# SCH_N3_FLIGHT_COMPUTER_2023-10-18_1.net
KiCad netlist of a schematic drawn in EasyEDA
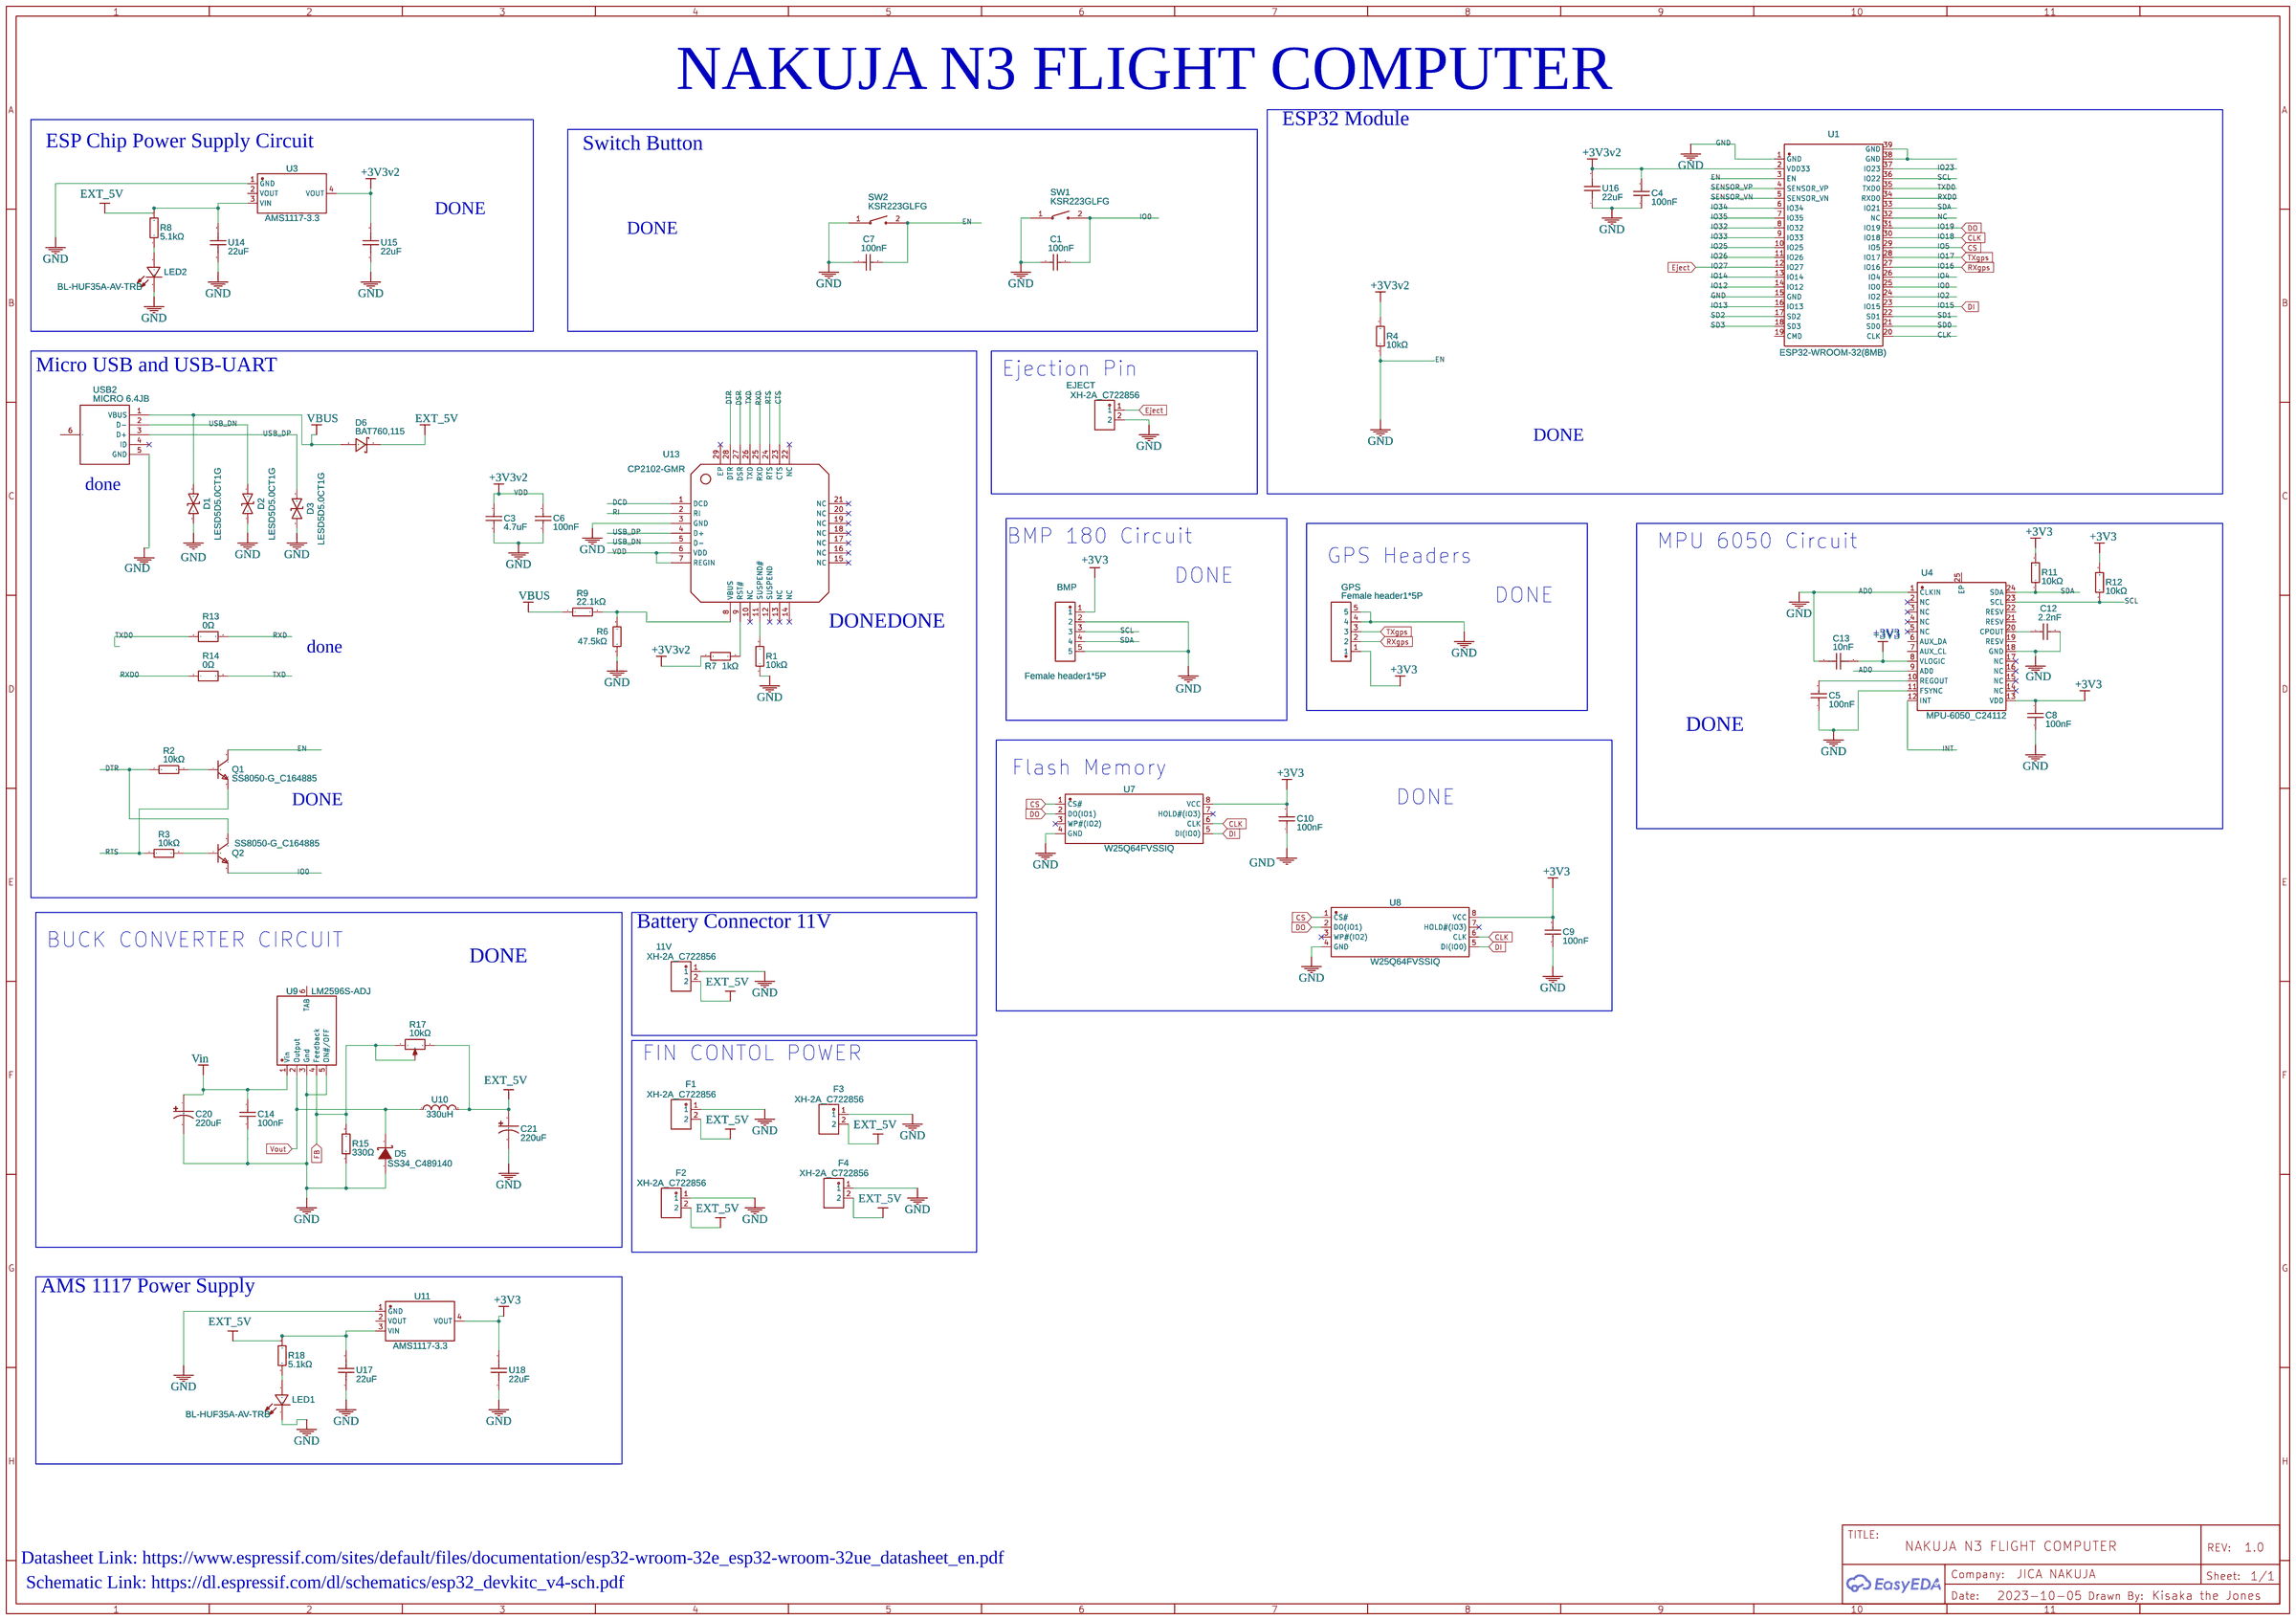
[diagram p0: schematic sheet]

(export (version "E")
  (design (tool "Eeschema 10.0.6"))
  (components
    (comp (ref "11V")
      (value "XH-2A_C722856")
      (fields (field (name "Manufacturer Part") "XH-2A") (field (name "Manufacturer") "CAX"))
      (libsource (lib "") (part "XH-2A_C722856_2"))
    )
    (comp (ref "BMP")
      (value "Female header1*5P")
      (fields (field (name "Manufacturer Part") "2.0-1*5P母") (field (name "Manufacturer") "BOOMELE(博穆精密)"))
      (libsource (lib "") (part "Female header1*5P"))
    )
    (comp (ref "C1")
      (value "100nF")
      (fields (field (name "Manufacturer Part") "FN15X104K160PNG") (field (name "Manufacturer") "PSA(信昌电陶)"))
      (libsource (lib "") (part "FN15X104K160PNG_1"))
    )
    (comp (ref "C3")
      (value "4.7uF")
      (fields
        (field (name "Manufacturer Part") "CL21B475KPFNNNE")
        (field (name "Manufacturer") "SAMSUNG(三星)")
      )
      (libsource (lib "") (part "CL21B475KPFNNNE"))
    )
    (comp (ref "C4")
      (value "100nF")
      (fields (field (name "Manufacturer Part") "FN15X104K160PNG") (field (name "Manufacturer") "PSA(信昌电陶)"))
      (libsource (lib "") (part "FN15X104K160PNG"))
    )
    (comp (ref "C5")
      (value "100nF")
      (fields (field (name "Manufacturer Part") "FN15X104K160PNG") (field (name "Manufacturer") "PSA(信昌电陶)"))
      (libsource (lib "") (part "FN15X104K160PNG"))
    )
    (comp (ref "C6")
      (value "100nF")
      (fields (field (name "Manufacturer Part") "FN15X104K160PNG") (field (name "Manufacturer") "PSA(信昌电陶)"))
      (libsource (lib "") (part "FN15X104K160PNG"))
    )
    (comp (ref "C7")
      (value "100nF")
      (fields (field (name "Manufacturer Part") "FN15X104K160PNG") (field (name "Manufacturer") "PSA(信昌电陶)"))
      (libsource (lib "") (part "FN15X104K160PNG_1"))
    )
    (comp (ref "C8")
      (value "100nF")
      (fields (field (name "Manufacturer Part") "FN15X104K160PNG") (field (name "Manufacturer") "PSA(信昌电陶)"))
      (libsource (lib "") (part "FN15X104K160PNG"))
    )
    (comp (ref "C9")
      (value "100nF")
      (fields (field (name "Manufacturer Part") "FN15X104K160PNG") (field (name "Manufacturer") "PSA(信昌电陶)"))
      (libsource (lib "") (part "FN15X104K160PNG"))
    )
    (comp (ref "C10")
      (value "100nF")
      (fields (field (name "Manufacturer Part") "FN15X104K160PNG") (field (name "Manufacturer") "PSA(信昌电陶)"))
      (libsource (lib "") (part "FN15X104K160PNG"))
    )
    (comp (ref "C12")
      (value "2.2nF")
      (fields (field (name "Manufacturer Part") "0805B222K500NT") (field (name "Manufacturer") "FH(风华)"))
      (libsource (lib "") (part "0805B222K500NT"))
    )
    (comp (ref "C13")
      (value "10nF")
      (fields
        (field (name "Manufacturer Part") "CC0805KRX7R9BB103")
        (field (name "Manufacturer") "YAGEO(国巨)")
      )
      (libsource (lib "") (part "CC0805KRX7R9BB103"))
    )
    (comp (ref "C14")
      (value "100nF")
      (fields (field (name "Manufacturer Part") "FN15X104K160PNG") (field (name "Manufacturer") "PSA(信昌电陶)"))
      (libsource (lib "") (part "FN15X104K160PNG"))
    )
    (comp (ref "C20")
      (value "220uF")
      (fields (field (name "Manufacturer Part") "EEEFP1H221AP") (field (name "Manufacturer") "PANASONIC(松下)"))
      (libsource (lib "") (part "EEEFP1H221AP"))
    )
    (comp (ref "C21")
      (value "220uF")
      (fields (field (name "Manufacturer Part") "EEEFP1H221AP") (field (name "Manufacturer") "PANASONIC(松下)"))
      (libsource (lib "") (part "EEEFP1H221AP"))
    )
    (comp (ref "D1")
      (value "LESD5D5.0CT1G")
      (fields (field (name "Manufacturer") "LRC(乐山无线电)"))
      (libsource (lib "") (part "LESD5D5.0CT1G"))
    )
    (comp (ref "D2")
      (value "LESD5D5.0CT1G")
      (fields (field (name "Manufacturer") "LRC(乐山无线电)"))
      (libsource (lib "") (part "LESD5D5.0CT1G"))
    )
    (comp (ref "D3")
      (value "LESD5D5.0CT1G")
      (fields (field (name "Manufacturer") "LRC(乐山无线电)"))
      (libsource (lib "") (part "LESD5D5.0CT1G"))
    )
    (comp (ref "D5")
      (value "SS34_C489140")
      (fields (field (name "Manufacturer Part") "SS34") (field (name "Manufacturer") "KEXIN(科信)"))
      (libsource (lib "") (part "SS34_C489140"))
    )
    (comp (ref "D6")
      (value "BAT760,115")
      (fields (field (name "Manufacturer") "Nexperia(安世)"))
      (libsource (lib "") (part "BAT760,115"))
    )
    (comp (ref "EJECT")
      (value "XH-2A_C722856")
      (fields (field (name "Manufacturer Part") "XH-2A") (field (name "Manufacturer") "CAX"))
      (libsource (lib "") (part "XH-2A_C722856_1"))
    )
    (comp (ref "F1")
      (value "XH-2A_C722856")
      (fields (field (name "Manufacturer Part") "XH-2A") (field (name "Manufacturer") "CAX"))
      (libsource (lib "") (part "XH-2A_C722856"))
    )
    (comp (ref "F2")
      (value "XH-2A_C722856")
      (fields (field (name "Manufacturer Part") "XH-2A") (field (name "Manufacturer") "CAX"))
      (libsource (lib "") (part "XH-2A_C722856"))
    )
    (comp (ref "F3")
      (value "XH-2A_C722856")
      (fields (field (name "Manufacturer Part") "XH-2A") (field (name "Manufacturer") "CAX"))
      (libsource (lib "") (part "XH-2A_C722856"))
    )
    (comp (ref "F4")
      (value "XH-2A_C722856")
      (fields (field (name "Manufacturer Part") "XH-2A") (field (name "Manufacturer") "CAX"))
      (libsource (lib "") (part "XH-2A_C722856"))
    )
    (comp (ref "GPS")
      (value "Female header1*5P")
      (fields (field (name "Manufacturer Part") "2.0-1*5P母") (field (name "Manufacturer") "BOOMELE(博穆精密)"))
      (libsource (lib "") (part "Female header1*5P_1"))
    )
    (comp (ref "LED1")
      (value "BL-HUF35A-AV-TRB")
      (fields (field (name "Manufacturer") "BrtLed(佰鸿)"))
      (libsource (lib "") (part "BL-HUF35A-AV-TRB"))
    )
    (comp (ref "LED2")
      (value "BL-HUF35A-AV-TRB")
      (fields (field (name "Manufacturer") "BrtLed(佰鸿)"))
      (libsource (lib "") (part "BL-HUF35A-AV-TRB"))
    )
    (comp (ref "Q1")
      (value "SS8050-G_C164885")
      (fields (field (name "Manufacturer Part") "SS8050-G") (field (name "Manufacturer") "CJ(江苏长电/长晶)"))
      (libsource (lib "") (part "SS8050-G_C164885"))
    )
    (comp (ref "Q2")
      (value "SS8050-G_C164885")
      (fields (field (name "Manufacturer Part") "SS8050-G") (field (name "Manufacturer") "CJ(江苏长电/长晶)"))
      (libsource (lib "") (part "SS8050-G_C164885"))
    )
    (comp (ref "R1")
      (value "10kΩ")
      (fields
        (field (name "Manufacturer Part") "QR1206J10K0P05Z")
        (field (name "Manufacturer") "EVER OHMS(天二科技)")
      )
      (libsource (lib "") (part "QR1206J10KP05_1"))
    )
    (comp (ref "R2")
      (value "10kΩ")
      (fields
        (field (name "Manufacturer Part") "QR1206J10K0P05Z")
        (field (name "Manufacturer") "EVER OHMS(天二科技)")
      )
      (libsource (lib "") (part "QR1206J10KP05"))
    )
    (comp (ref "R3")
      (value "10kΩ")
      (fields
        (field (name "Manufacturer Part") "QR1206J10K0P05Z")
        (field (name "Manufacturer") "EVER OHMS(天二科技)")
      )
      (libsource (lib "") (part "QR1206J10KP05"))
    )
    (comp (ref "R4")
      (value "10kΩ")
      (fields
        (field (name "Manufacturer Part") "QR1206J10K0P05Z")
        (field (name "Manufacturer") "EVER OHMS(天二科技)")
      )
      (libsource (lib "") (part "QR1206J10KP05_1"))
    )
    (comp (ref "R6")
      (value "47.5kΩ")
      (fields
        (field (name "Manufacturer Part") "0402WGF4752TCE")
        (field (name "Manufacturer") "UNI-ROYAL(厚声)")
      )
      (libsource (lib "") (part "0402WGF4752TCE"))
    )
    (comp (ref "R7")
      (value "1kΩ")
      (fields
        (field (name "Manufacturer Part") "0402WGF1001TCE")
        (field (name "Manufacturer") "UNI-ROYAL(厚声)")
      )
      (libsource (lib "") (part "0402WGF1001TCE"))
    )
    (comp (ref "R8")
      (value "5.1kΩ")
      (fields
        (field (name "Manufacturer Part") "0402WGJ0512TCE")
        (field (name "Manufacturer") "UNI-ROYAL(厚声)")
      )
      (libsource (lib "") (part "0402WGJ0512TCE"))
    )
    (comp (ref "R9")
      (value "22.1kΩ")
      (fields
        (field (name "Manufacturer Part") "0402WGF2212TCE")
        (field (name "Manufacturer") "UNI-ROYAL(厚声)")
      )
      (libsource (lib "") (part "0402WGF2212TCE"))
    )
    (comp (ref "R11")
      (value "10kΩ")
      (fields
        (field (name "Manufacturer Part") "QR1206J10K0P05Z")
        (field (name "Manufacturer") "EVER OHMS(天二科技)")
      )
      (libsource (lib "") (part "QR1206J10KP05_1"))
    )
    (comp (ref "R12")
      (value "10kΩ")
      (fields
        (field (name "Manufacturer Part") "QR1206J10K0P05Z")
        (field (name "Manufacturer") "EVER OHMS(天二科技)")
      )
      (libsource (lib "") (part "QR1206J10KP05_1"))
    )
    (comp (ref "R13")
      (value "0Ω")
      (fields
        (field (name "Manufacturer Part") "CR0402F0R00Q10Z")
        (field (name "Manufacturer") "EVER OHMS(天二科技)")
      )
      (libsource (lib "") (part "CR0402F0R00Q10Z"))
    )
    (comp (ref "R14")
      (value "0Ω")
      (fields
        (field (name "Manufacturer Part") "CR0402F0R00Q10Z")
        (field (name "Manufacturer") "EVER OHMS(天二科技)")
      )
      (libsource (lib "") (part "CR0402F0R00Q10Z"))
    )
    (comp (ref "R15")
      (value "330Ω")
      (fields (field (name "Manufacturer Part") "RK73B1JTTD331J") (field (name "Manufacturer") "KOA"))
      (libsource (lib "") (part "RK73B1JTTD331J"))
    )
    (comp (ref "R17")
      (value "10kΩ")
      (fields (field (name "Manufacturer Part") "3296W-1-103LF") (field (name "Manufacturer") "BOURNS"))
      (libsource (lib "") (part "3296W-1-103LF"))
    )
    (comp (ref "R18")
      (value "5.1kΩ")
      (fields
        (field (name "Manufacturer Part") "0402WGJ0512TCE")
        (field (name "Manufacturer") "UNI-ROYAL(厚声)")
      )
      (libsource (lib "") (part "0402WGJ0512TCE"))
    )
    (comp (ref "SW1")
      (value "KSR223GLFG")
      (fields (field (name "Manufacturer") "C&K"))
      (libsource (lib "") (part "KSR223GLFG"))
    )
    (comp (ref "SW2")
      (value "KSR223GLFG")
      (fields (field (name "Manufacturer") "C&K"))
      (libsource (lib "") (part "KSR223GLFG"))
    )
    (comp (ref "U1")
      (value "ESP32-WROOM-32(8MB)")
      (fields
        (field (name "Manufacturer Part") "ESP32-WROOM-32-N8")
        (field (name "Manufacturer") "ESPRESSIF(乐鑫)")
      )
      (libsource (lib "") (part "ESP32-WROOM-32(8MB)"))
    )
    (comp (ref "U3")
      (value "AMS1117-3.3")
      (fields (field (name "Manufacturer") "AMS"))
      (libsource (lib "") (part "AMS1117-3.3"))
    )
    (comp (ref "U4")
      (value "MPU-6050_C24112")
      (fields
        (field (name "Manufacturer Part") "MPU-6050")
        (field (name "Manufacturer") "TDK InvenSense(应美盛)")
      )
      (libsource (lib "") (part "MPU-6050_C24112"))
    )
    (comp (ref "U7")
      (value "W25Q64FVSSIQ")
      (fields (field (name "Manufacturer") "WINBOND(华邦)"))
      (libsource (lib "") (part "W25Q64FVSSIQ"))
    )
    (comp (ref "U8")
      (value "W25Q64FVSSIQ")
      (fields (field (name "Manufacturer") "WINBOND(华邦)"))
      (libsource (lib "") (part "W25Q64FVSSIQ"))
    )
    (comp (ref "U9")
      (value "LM2596S-ADJ")
      (fields (field (name "Manufacturer") "UMW(友台半导体)"))
      (libsource (lib "") (part "LM2596S-ADJ"))
    )
    (comp (ref "U10")
      (value "330uH")
      (fields (field (name "Manufacturer Part") "SLF12575T-331M1R0-H") (field (name "Manufacturer") "TDK"))
      (libsource (lib "") (part "SLF12575T-331M1R0-H"))
    )
    (comp (ref "U11")
      (value "AMS1117-3.3")
      (fields (field (name "Manufacturer") "AMS"))
      (libsource (lib "") (part "AMS1117-3.3"))
    )
    (comp (ref "U13")
      (value "CP2102-GMR")
      (fields (field (name "Manufacturer") "SILICON LABS(芯科)"))
      (libsource (lib "") (part "CP2102-GMR"))
    )
    (comp (ref "U14")
      (value "22uF")
      (fields
        (field (name "Manufacturer Part") "V226M0805X5R100NHP")
        (field (name "Manufacturer") "VIIYONG(微容)")
      )
      (libsource (lib "") (part "V226M0805X5R100NHP"))
    )
    (comp (ref "U15")
      (value "22uF")
      (fields
        (field (name "Manufacturer Part") "V226M0805X5R100NHP")
        (field (name "Manufacturer") "VIIYONG(微容)")
      )
      (libsource (lib "") (part "V226M0805X5R100NHP"))
    )
    (comp (ref "U16")
      (value "22uF")
      (fields
        (field (name "Manufacturer Part") "V226M0805X5R100NHP")
        (field (name "Manufacturer") "VIIYONG(微容)")
      )
      (libsource (lib "") (part "V226M0805X5R100NHP"))
    )
    (comp (ref "U17")
      (value "22uF")
      (fields
        (field (name "Manufacturer Part") "V226M0805X5R100NHP")
        (field (name "Manufacturer") "VIIYONG(微容)")
      )
      (libsource (lib "") (part "V226M0805X5R100NHP"))
    )
    (comp (ref "U18")
      (value "22uF")
      (fields
        (field (name "Manufacturer Part") "V226M0805X5R100NHP")
        (field (name "Manufacturer") "VIIYONG(微容)")
      )
      (libsource (lib "") (part "V226M0805X5R100NHP"))
    )
    (comp (ref "USB2")
      (value "MICRO 6.4JB")
      (fields (field (name "Manufacturer") "SHOU HAN(首韩)"))
      (libsource (lib "") (part "MICRO 6.4JB"))
    )
  )
  (nets
    (net (code "1") (name "+3V3") (class "Default")
      (node (ref "BMP") (pin "1") (pinfunction "1_1") (pintype "unspecified"))
      (node (ref "C10") (pin "2") (pinfunction "2_2") (pintype "input"))
      (node (ref "C13") (pin "2") (pinfunction "2_2") (pintype "unspecified"))
      (node (ref "C8") (pin "2") (pinfunction "2_2") (pintype "input"))
      (node (ref "C9") (pin "2") (pinfunction "2_2") (pintype "input"))
      (node (ref "GPS") (pin "1") (pinfunction "1_1") (pintype "unspecified"))
      (node (ref "R11") (pin "2") (pinfunction "2_2") (pintype "unspecified"))
      (node (ref "R12") (pin "2") (pinfunction "2_2") (pintype "unspecified"))
      (node (ref "U11") (pin "4") (pinfunction "VOUT_4") (pintype "unspecified"))
      (node (ref "U18") (pin "2") (pinfunction "2_2") (pintype "unspecified"))
      (node (ref "U4") (pin "13") (pinfunction "VDD_13") (pintype "unspecified"))
      (node (ref "U4") (pin "8") (pinfunction "VLOGIC_8") (pintype "unspecified"))
      (node (ref "U7") (pin "8") (pinfunction "VCC_8") (pintype "unspecified"))
      (node (ref "U8") (pin "8") (pinfunction "VCC_8") (pintype "unspecified"))
    )
    (net (code "2") (name "+3V3v2") (class "Default")
      (node (ref "C3") (pin "2") (pinfunction "2_2") (pintype "input"))
      (node (ref "C4") (pin "2") (pinfunction "2_2") (pintype "input"))
      (node (ref "C6") (pin "2") (pinfunction "2_2") (pintype "input"))
      (node (ref "R4") (pin "2") (pinfunction "2_2") (pintype "unspecified"))
      (node (ref "R7") (pin "1") (pinfunction "1_1") (pintype "input"))
      (node (ref "U1") (pin "2") (pinfunction "VDD33_2") (pintype "unspecified"))
      (node (ref "U13") (pin "6") (pinfunction "VDD_6") (pintype "unspecified"))
      (node (ref "U13") (pin "7") (pinfunction "REGIN_7") (pintype "unspecified"))
      (node (ref "U15") (pin "2") (pinfunction "2_2") (pintype "unspecified"))
      (node (ref "U16") (pin "2") (pinfunction "2_2") (pintype "unspecified"))
      (node (ref "U3") (pin "4") (pinfunction "VOUT_4") (pintype "unspecified"))
    )
    (net (code "3") (name "/CTS") (class "Default")
      (node (ref "U13") (pin "23") (pinfunction "CTS_23") (pintype "unspecified"))
    )
    (net (code "4") (name "/DCD") (class "Default")
      (node (ref "U13") (pin "1") (pinfunction "DCD_1") (pintype "unspecified"))
    )
    (net (code "5") (name "/DSR") (class "Default")
      (node (ref "U13") (pin "27") (pinfunction "DSR_27") (pintype "unspecified"))
    )
    (net (code "6") (name "/DTR") (class "Default")
      (node (ref "Q2") (pin "3") (pinfunction "C_3") (pintype "unspecified"))
      (node (ref "R2") (pin "1") (pinfunction "1_1") (pintype "unspecified"))
      (node (ref "U13") (pin "28") (pinfunction "DTR_28") (pintype "unspecified"))
    )
    (net (code "7") (name "/INT") (class "Default")
      (node (ref "U4") (pin "12") (pinfunction "INT_12") (pintype "unspecified"))
    )
    (net (code "8") (name "/IO0") (class "Default")
      (node (ref "C1") (pin "2") (pinfunction "2_2") (pintype "input"))
      (node (ref "Q2") (pin "2") (pinfunction "E_2") (pintype "unspecified"))
      (node (ref "SW1") (pin "2") (pinfunction "2_2") (pintype "unspecified"))
      (node (ref "U1") (pin "25") (pinfunction "IO0_25") (pintype "unspecified"))
    )
    (net (code "9") (name "/IO2") (class "Default")
      (node (ref "U1") (pin "24") (pinfunction "IO2_24") (pintype "unspecified"))
    )
    (net (code "10") (name "/IO4") (class "Default")
      (node (ref "U1") (pin "26") (pinfunction "IO4_26") (pintype "unspecified"))
    )
    (net (code "11") (name "/IO12") (class "Default")
      (node (ref "U1") (pin "14") (pinfunction "IO12_14") (pintype "unspecified"))
    )
    (net (code "12") (name "/IO13") (class "Default")
      (node (ref "U1") (pin "16") (pinfunction "IO13_16") (pintype "unspecified"))
    )
    (net (code "13") (name "/IO14") (class "Default")
      (node (ref "U1") (pin "13") (pinfunction "IO14_13") (pintype "unspecified"))
    )
    (net (code "14") (name "/IO23") (class "Default")
      (node (ref "U1") (pin "37") (pinfunction "IO23_37") (pintype "unspecified"))
    )
    (net (code "15") (name "/IO25") (class "Default")
      (node (ref "U1") (pin "10") (pinfunction "IO25_10") (pintype "unspecified"))
    )
    (net (code "16") (name "/IO26") (class "Default")
      (node (ref "U1") (pin "11") (pinfunction "IO26_11") (pintype "unspecified"))
    )
    (net (code "17") (name "/IO32") (class "Default")
      (node (ref "U1") (pin "8") (pinfunction "IO32_8") (pintype "unspecified"))
    )
    (net (code "18") (name "/IO33") (class "Default")
      (node (ref "U1") (pin "9") (pinfunction "IO33_9") (pintype "unspecified"))
    )
    (net (code "19") (name "/IO34") (class "Default")
      (node (ref "U1") (pin "6") (pinfunction "IO34_6") (pintype "unspecified"))
    )
    (net (code "20") (name "/IO35") (class "Default")
      (node (ref "U1") (pin "7") (pinfunction "IO35_7") (pintype "unspecified"))
    )
    (net (code "21") (name "/NC") (class "Default")
      (node (ref "U1") (pin "32") (pinfunction "NC_32") (pintype "unspecified"))
    )
    (net (code "22") (name "/RI") (class "Default")
      (node (ref "U13") (pin "2") (pinfunction "RI_2") (pintype "unspecified"))
    )
    (net (code "23") (name "/RTS") (class "Default")
      (node (ref "Q1") (pin "2") (pinfunction "E_2") (pintype "unspecified"))
      (node (ref "R3") (pin "1") (pinfunction "1_1") (pintype "unspecified"))
      (node (ref "U13") (pin "24") (pinfunction "RTS_24") (pintype "unspecified"))
    )
    (net (code "24") (name "/RXD") (class "Default")
      (node (ref "R13") (pin "2") (pinfunction "2_2") (pintype "unspecified"))
      (node (ref "U13") (pin "25") (pinfunction "RXD_25") (pintype "unspecified"))
    )
    (net (code "25") (name "/RXD0") (class "Default")
      (node (ref "R14") (pin "1") (pinfunction "1_1") (pintype "unspecified"))
      (node (ref "U1") (pin "34") (pinfunction "RXD0_34") (pintype "unspecified"))
    )
    (net (code "26") (name "/SCL") (class "Default")
      (node (ref "BMP") (pin "3") (pinfunction "3_3") (pintype "unspecified"))
      (node (ref "R12") (pin "1") (pinfunction "1_1") (pintype "unspecified"))
      (node (ref "U1") (pin "36") (pinfunction "IO22_36") (pintype "unspecified"))
      (node (ref "U4") (pin "23") (pinfunction "SCL_23") (pintype "unspecified"))
    )
    (net (code "27") (name "/SD0") (class "Default")
      (node (ref "U1") (pin "21") (pinfunction "SD0_21") (pintype "unspecified"))
    )
    (net (code "28") (name "/SD1") (class "Default")
      (node (ref "U1") (pin "22") (pinfunction "SD1_22") (pintype "unspecified"))
    )
    (net (code "29") (name "/SD2") (class "Default")
      (node (ref "U1") (pin "17") (pinfunction "SD2_17") (pintype "unspecified"))
    )
    (net (code "30") (name "/SD3") (class "Default")
      (node (ref "U1") (pin "18") (pinfunction "SD3_18") (pintype "unspecified"))
    )
    (net (code "31") (name "/SDA") (class "Default")
      (node (ref "BMP") (pin "4") (pinfunction "4_4") (pintype "unspecified"))
      (node (ref "R11") (pin "1") (pinfunction "1_1") (pintype "unspecified"))
      (node (ref "U1") (pin "33") (pinfunction "IO21_33") (pintype "unspecified"))
      (node (ref "U4") (pin "24") (pinfunction "SDA_24") (pintype "unspecified"))
    )
    (net (code "32") (name "/SENSOR_VN") (class "Default")
      (node (ref "U1") (pin "5") (pinfunction "SENSOR_VN_5") (pintype "unspecified"))
    )
    (net (code "33") (name "/SENSOR_VP") (class "Default")
      (node (ref "U1") (pin "4") (pinfunction "SENSOR_VP_4") (pintype "unspecified"))
    )
    (net (code "34") (name "/TXD") (class "Default")
      (node (ref "R14") (pin "2") (pinfunction "2_2") (pintype "unspecified"))
      (node (ref "U13") (pin "26") (pinfunction "TXD_26") (pintype "unspecified"))
    )
    (net (code "35") (name "/TXD0") (class "Default")
      (node (ref "R13") (pin "1") (pinfunction "1_1") (pintype "unspecified"))
      (node (ref "U1") (pin "35") (pinfunction "TXD0_35") (pintype "unspecified"))
    )
    (net (code "36") (name "/USB_DN") (class "Default")
      (node (ref "D2") (pin "2") (pinfunction "2_2") (pintype "unspecified"))
      (node (ref "U13") (pin "5") (pinfunction "D-_5") (pintype "unspecified"))
      (node (ref "USB2") (pin "2") (pinfunction "D-_2") (pintype "input"))
    )
    (net (code "37") (name "/USB_DP") (class "Default")
      (node (ref "D3") (pin "2") (pinfunction "2_2") (pintype "unspecified"))
      (node (ref "U13") (pin "4") (pinfunction "D+_4") (pintype "unspecified"))
      (node (ref "USB2") (pin "3") (pinfunction "D+_3") (pintype "input"))
    )
    (net (code "38") (name "CLK") (class "Default")
      (node (ref "U1") (pin "20") (pinfunction "CLK_20") (pintype "unspecified"))
      (node (ref "U1") (pin "30") (pinfunction "IO18_30") (pintype "unspecified"))
      (node (ref "U7") (pin "6") (pinfunction "CLK_6") (pintype "unspecified"))
      (node (ref "U8") (pin "6") (pinfunction "CLK_6") (pintype "unspecified"))
    )
    (net (code "39") (name "CS") (class "Default")
      (node (ref "U1") (pin "29") (pinfunction "IO5_29") (pintype "unspecified"))
      (node (ref "U7") (pin "1") (pinfunction "CS#_1") (pintype "unspecified"))
      (node (ref "U8") (pin "1") (pinfunction "CS#_1") (pintype "unspecified"))
    )
    (net (code "40") (name "DI") (class "Default")
      (node (ref "U1") (pin "23") (pinfunction "IO15_23") (pintype "unspecified"))
      (node (ref "U7") (pin "5") (pinfunction "DI(IO0)_5") (pintype "unspecified"))
      (node (ref "U8") (pin "5") (pinfunction "DI(IO0)_5") (pintype "unspecified"))
    )
    (net (code "41") (name "DO") (class "Default")
      (node (ref "U1") (pin "31") (pinfunction "IO19_31") (pintype "unspecified"))
      (node (ref "U7") (pin "2") (pinfunction "DO(IO1)_2") (pintype "unspecified"))
      (node (ref "U8") (pin "2") (pinfunction "DO(IO1)_2") (pintype "unspecified"))
    )
    (net (code "42") (name "EXT_5V") (class "Default")
      (node (ref "11V") (pin "2") (pinfunction "2_2") (pintype "unspecified"))
      (node (ref "C21") (pin "1") (pinfunction "1_1") (pintype "unspecified"))
      (node (ref "D6") (pin "1") (pinfunction "K_1") (pintype "unspecified"))
      (node (ref "F1") (pin "2") (pinfunction "2_2") (pintype "unspecified"))
      (node (ref "F2") (pin "2") (pinfunction "2_2") (pintype "unspecified"))
      (node (ref "F3") (pin "2") (pinfunction "2_2") (pintype "unspecified"))
      (node (ref "F4") (pin "2") (pinfunction "2_2") (pintype "unspecified"))
      (node (ref "R17") (pin "3") (pinfunction "3_3") (pintype "input"))
      (node (ref "R18") (pin "2") (pinfunction "2_2") (pintype "input"))
      (node (ref "R8") (pin "2") (pinfunction "2_2") (pintype "input"))
      (node (ref "U10") (pin "2") (pinfunction "2_2") (pintype "unspecified"))
      (node (ref "U11") (pin "3") (pinfunction "VIN_3") (pintype "unspecified"))
      (node (ref "U14") (pin "2") (pinfunction "2_2") (pintype "unspecified"))
      (node (ref "U17") (pin "2") (pinfunction "2_2") (pintype "unspecified"))
      (node (ref "U3") (pin "3") (pinfunction "VIN_3") (pintype "unspecified"))
    )
    (net (code "43") (name "Eject") (class "Default")
      (node (ref "EJECT") (pin "1") (pinfunction "1_1") (pintype "unspecified"))
      (node (ref "U1") (pin "12") (pinfunction "IO27_12") (pintype "unspecified"))
    )
    (net (code "44") (name "FB") (class "Default")
      (node (ref "R15") (pin "2") (pinfunction "2_2") (pintype "input"))
      (node (ref "R17") (pin "1") (pinfunction "1_1") (pintype "input"))
      (node (ref "R17") (pin "2") (pinfunction "2_2") (pintype "input"))
      (node (ref "U9") (pin "4") (pinfunction "Feedback_4") (pintype "unspecified"))
    )
    (net (code "45") (name "GND") (class "Default")
      (node (ref "11V") (pin "1") (pinfunction "1_1") (pintype "unspecified"))
      (node (ref "BMP") (pin "2") (pinfunction "2_2") (pintype "unspecified"))
      (node (ref "BMP") (pin "5") (pinfunction "5_5") (pintype "unspecified"))
      (node (ref "C1") (pin "1") (pinfunction "1_1") (pintype "input"))
      (node (ref "C10") (pin "1") (pinfunction "1_1") (pintype "input"))
      (node (ref "C12") (pin "2") (pinfunction "2_2") (pintype "input"))
      (node (ref "C13") (pin "1") (pinfunction "1_1") (pintype "unspecified"))
      (node (ref "C14") (pin "1") (pinfunction "1_1") (pintype "input"))
      (node (ref "C20") (pin "2") (pinfunction "2_2") (pintype "unspecified"))
      (node (ref "C21") (pin "2") (pinfunction "2_2") (pintype "unspecified"))
      (node (ref "C3") (pin "1") (pinfunction "1_1") (pintype "input"))
      (node (ref "C4") (pin "1") (pinfunction "1_1") (pintype "input"))
      (node (ref "C5") (pin "1") (pinfunction "1_1") (pintype "input"))
      (node (ref "C6") (pin "1") (pinfunction "1_1") (pintype "input"))
      (node (ref "C7") (pin "1") (pinfunction "1_1") (pintype "input"))
      (node (ref "C7") (pin "2") (pinfunction "2_2") (pintype "input"))
      (node (ref "C8") (pin "1") (pinfunction "1_1") (pintype "input"))
      (node (ref "C9") (pin "1") (pinfunction "1_1") (pintype "input"))
      (node (ref "D1") (pin "1") (pinfunction "1_1") (pintype "unspecified"))
      (node (ref "D2") (pin "1") (pinfunction "1_1") (pintype "unspecified"))
      (node (ref "D3") (pin "1") (pinfunction "1_1") (pintype "unspecified"))
      (node (ref "D5") (pin "2") (pinfunction "A_2") (pintype "unspecified"))
      (node (ref "EJECT") (pin "2") (pinfunction "2_2") (pintype "unspecified"))
      (node (ref "F1") (pin "1") (pinfunction "1_1") (pintype "unspecified"))
      (node (ref "F2") (pin "1") (pinfunction "1_1") (pintype "unspecified"))
      (node (ref "F3") (pin "1") (pinfunction "1_1") (pintype "unspecified"))
      (node (ref "F4") (pin "1") (pinfunction "1_1") (pintype "unspecified"))
      (node (ref "GPS") (pin "4") (pinfunction "4_4") (pintype "unspecified"))
      (node (ref "GPS") (pin "5") (pinfunction "5_5") (pintype "unspecified"))
      (node (ref "LED1") (pin "1") (pinfunction "C_1") (pintype "unspecified"))
      (node (ref "LED2") (pin "1") (pinfunction "C_1") (pintype "unspecified"))
      (node (ref "Q1") (pin "3") (pinfunction "C_3") (pintype "unspecified"))
      (node (ref "R1") (pin "1") (pinfunction "1_1") (pintype "unspecified"))
      (node (ref "R15") (pin "1") (pinfunction "1_1") (pintype "input"))
      (node (ref "R4") (pin "1") (pinfunction "1_1") (pintype "unspecified"))
      (node (ref "R6") (pin "1") (pinfunction "1_1") (pintype "input"))
      (node (ref "SW1") (pin "1") (pinfunction "1_1") (pintype "unspecified"))
      (node (ref "SW2") (pin "1") (pinfunction "1_1") (pintype "unspecified"))
      (node (ref "SW2") (pin "2") (pinfunction "2_2") (pintype "unspecified"))
      (node (ref "U1") (pin "1") (pinfunction "GND_1") (pintype "unspecified"))
      (node (ref "U1") (pin "15") (pinfunction "GND_15") (pintype "unspecified"))
      (node (ref "U1") (pin "3") (pinfunction "EN_3") (pintype "unspecified"))
      (node (ref "U11") (pin "1") (pinfunction "GND_1") (pintype "unspecified"))
      (node (ref "U13") (pin "3") (pinfunction "GND_3") (pintype "unspecified"))
      (node (ref "U14") (pin "1") (pinfunction "1_1") (pintype "unspecified"))
      (node (ref "U15") (pin "1") (pinfunction "1_1") (pintype "unspecified"))
      (node (ref "U16") (pin "1") (pinfunction "1_1") (pintype "unspecified"))
      (node (ref "U17") (pin "1") (pinfunction "1_1") (pintype "unspecified"))
      (node (ref "U18") (pin "1") (pinfunction "1_1") (pintype "unspecified"))
      (node (ref "U3") (pin "1") (pinfunction "GND_1") (pintype "unspecified"))
      (node (ref "U4") (pin "1") (pinfunction "CLKIN_1") (pintype "unspecified"))
      (node (ref "U4") (pin "11") (pinfunction "FSYNC_11") (pintype "unspecified"))
      (node (ref "U4") (pin "18") (pinfunction "GND_18") (pintype "unspecified"))
      (node (ref "U4") (pin "9") (pinfunction "AD0_9") (pintype "unspecified"))
      (node (ref "U7") (pin "4") (pinfunction "GND_4") (pintype "unspecified"))
      (node (ref "U8") (pin "4") (pinfunction "GND_4") (pintype "unspecified"))
      (node (ref "U9") (pin "3") (pinfunction "Gnd_3") (pintype "unspecified"))
      (node (ref "U9") (pin "5") (pinfunction "ON#/OFF_5") (pintype "unspecified"))
      (node (ref "USB2") (pin "5") (pinfunction "GND_5") (pintype "input"))
    )
    (net (code "46") (name "Net-(LED1-A)") (class "Default")
      (node (ref "LED1") (pin "2") (pinfunction "A_2") (pintype "unspecified"))
      (node (ref "R18") (pin "1") (pinfunction "1_1") (pintype "input"))
    )
    (net (code "47") (name "Net-(LED2-A)") (class "Default")
      (node (ref "LED2") (pin "2") (pinfunction "A_2") (pintype "unspecified"))
      (node (ref "R8") (pin "1") (pinfunction "1_1") (pintype "input"))
    )
    (net (code "48") (name "Net-(Q1-B)") (class "Default")
      (node (ref "Q1") (pin "1") (pinfunction "B_1") (pintype "unspecified"))
      (node (ref "R2") (pin "2") (pinfunction "2_2") (pintype "unspecified"))
    )
    (net (code "49") (name "Net-(Q2-B)") (class "Default")
      (node (ref "Q2") (pin "1") (pinfunction "B_1") (pintype "unspecified"))
      (node (ref "R3") (pin "2") (pinfunction "2_2") (pintype "unspecified"))
    )
    (net (code "50") (name "Net-(U1-GND-Pad38)") (class "Default")
      (node (ref "U1") (pin "38") (pinfunction "GND_38") (pintype "unspecified"))
      (node (ref "U1") (pin "39") (pinfunction "GND_39") (pintype "unspecified"))
    )
    (net (code "51") (name "Net-(U4-CPOUT)") (class "Default")
      (node (ref "C12") (pin "1") (pinfunction "1_1") (pintype "input"))
      (node (ref "U4") (pin "20") (pinfunction "CPOUT_20") (pintype "unspecified"))
    )
    (net (code "52") (name "Net-(U4-REGOUT)") (class "Default")
      (node (ref "C5") (pin "2") (pinfunction "2_2") (pintype "input"))
      (node (ref "U4") (pin "10") (pinfunction "REGOUT_10") (pintype "unspecified"))
    )
    (net (code "53") (name "Net-(U13-RST#)") (class "Default")
      (node (ref "R7") (pin "2") (pinfunction "2_2") (pintype "input"))
      (node (ref "U13") (pin "9") (pinfunction "RST#_9") (pintype "unspecified"))
    )
    (net (code "54") (name "Net-(U13-SUSPEND#)") (class "Default")
      (node (ref "R1") (pin "2") (pinfunction "2_2") (pintype "unspecified"))
      (node (ref "U13") (pin "11") (pinfunction "SUSPEND#_11") (pintype "unspecified"))
    )
    (net (code "55") (name "Net-(U13-VBUS)") (class "Default")
      (node (ref "R6") (pin "2") (pinfunction "2_2") (pintype "input"))
      (node (ref "R9") (pin "2") (pinfunction "2_2") (pintype "input"))
      (node (ref "U13") (pin "8") (pinfunction "VBUS_8") (pintype "unspecified"))
    )
    (net (code "56") (name "RXgps") (class "Default")
      (node (ref "GPS") (pin "2") (pinfunction "2_2") (pintype "unspecified"))
      (node (ref "U1") (pin "27") (pinfunction "IO16_27") (pintype "unspecified"))
    )
    (net (code "57") (name "TXgps") (class "Default")
      (node (ref "GPS") (pin "3") (pinfunction "3_3") (pintype "unspecified"))
      (node (ref "U1") (pin "28") (pinfunction "IO17_28") (pintype "unspecified"))
    )
    (net (code "58") (name "VBUS") (class "Default")
      (node (ref "D1") (pin "2") (pinfunction "2_2") (pintype "unspecified"))
      (node (ref "D6") (pin "2") (pinfunction "A_2") (pintype "unspecified"))
      (node (ref "R9") (pin "1") (pinfunction "1_1") (pintype "input"))
      (node (ref "USB2") (pin "1") (pinfunction "VBUS_1") (pintype "input"))
    )
    (net (code "59") (name "Vin") (class "Default")
      (node (ref "C14") (pin "2") (pinfunction "2_2") (pintype "input"))
      (node (ref "C20") (pin "1") (pinfunction "1_1") (pintype "unspecified"))
      (node (ref "U9") (pin "1") (pinfunction "Vin_1") (pintype "unspecified"))
    )
    (net (code "60") (name "Vout") (class "Default")
      (node (ref "D5") (pin "1") (pinfunction "K_1") (pintype "unspecified"))
      (node (ref "U10") (pin "1") (pinfunction "1_1") (pintype "unspecified"))
      (node (ref "U9") (pin "2") (pinfunction "Output_2") (pintype "unspecified"))
    )
    (net (code "61") (name "unconnected-(U1-CMD-Pad19)") (class "Default")
      (node (ref "U1") (pin "19") (pinfunction "CMD_19") (pintype "unspecified"))
    )
    (net (code "62") (name "unconnected-(U3-VOUT-Pad2)") (class "Default")
      (node (ref "U3") (pin "2") (pinfunction "VOUT_2") (pintype "unspecified"))
    )
    (net (code "63") (name "unconnected-(U4-AUX_CL-Pad7)") (class "Default")
      (node (ref "U4") (pin "7") (pinfunction "AUX_CL_7") (pintype "unspecified"))
    )
    (net (code "64") (name "unconnected-(U4-AUX_DA-Pad6)") (class "Default")
      (node (ref "U4") (pin "6") (pinfunction "AUX_DA_6") (pintype "unspecified"))
    )
    (net (code "65") (name "unconnected-(U4-EP-Pad25)") (class "Default")
      (node (ref "U4") (pin "25") (pinfunction "EP_25") (pintype "unspecified"))
    )
    (net (code "66") (name "unconnected-(U4-NC-Pad2)") (class "Default")
      (node (ref "U4") (pin "2") (pinfunction "NC_2") (pintype "unspecified+no_connect"))
    )
    (net (code "67") (name "unconnected-(U4-NC-Pad3)") (class "Default")
      (node (ref "U4") (pin "3") (pinfunction "NC_3") (pintype "unspecified+no_connect"))
    )
    (net (code "68") (name "unconnected-(U4-NC-Pad4)") (class "Default")
      (node (ref "U4") (pin "4") (pinfunction "NC_4") (pintype "unspecified+no_connect"))
    )
    (net (code "69") (name "unconnected-(U4-NC-Pad5)") (class "Default")
      (node (ref "U4") (pin "5") (pinfunction "NC_5") (pintype "unspecified+no_connect"))
    )
    (net (code "70") (name "unconnected-(U4-NC-Pad14)") (class "Default")
      (node (ref "U4") (pin "14") (pinfunction "NC_14") (pintype "unspecified+no_connect"))
    )
    (net (code "71") (name "unconnected-(U4-NC-Pad15)") (class "Default")
      (node (ref "U4") (pin "15") (pinfunction "NC_15") (pintype "unspecified+no_connect"))
    )
    (net (code "72") (name "unconnected-(U4-NC-Pad16)") (class "Default")
      (node (ref "U4") (pin "16") (pinfunction "NC_16") (pintype "unspecified+no_connect"))
    )
    (net (code "73") (name "unconnected-(U4-NC-Pad17)") (class "Default")
      (node (ref "U4") (pin "17") (pinfunction "NC_17") (pintype "unspecified+no_connect"))
    )
    (net (code "74") (name "unconnected-(U4-RESV-Pad19)") (class "Default")
      (node (ref "U4") (pin "19") (pinfunction "RESV_19") (pintype "unspecified"))
    )
    (net (code "75") (name "unconnected-(U4-RESV-Pad21)") (class "Default")
      (node (ref "U4") (pin "21") (pinfunction "RESV_21") (pintype "unspecified"))
    )
    (net (code "76") (name "unconnected-(U4-RESV-Pad22)") (class "Default")
      (node (ref "U4") (pin "22") (pinfunction "RESV_22") (pintype "unspecified"))
    )
    (net (code "77") (name "unconnected-(U7-HOLD#(IO3)-Pad7)") (class "Default")
      (node (ref "U7") (pin "7") (pinfunction "HOLD#(IO3)_7") (pintype "unspecified+no_connect"))
    )
    (net (code "78") (name "unconnected-(U7-WP#(IO2)-Pad3)") (class "Default")
      (node (ref "U7") (pin "3") (pinfunction "WP#(IO2)_3") (pintype "unspecified+no_connect"))
    )
    (net (code "79") (name "unconnected-(U8-HOLD#(IO3)-Pad7)") (class "Default")
      (node (ref "U8") (pin "7") (pinfunction "HOLD#(IO3)_7") (pintype "unspecified+no_connect"))
    )
    (net (code "80") (name "unconnected-(U8-WP#(IO2)-Pad3)") (class "Default")
      (node (ref "U8") (pin "3") (pinfunction "WP#(IO2)_3") (pintype "unspecified+no_connect"))
    )
    (net (code "81") (name "unconnected-(U9-TAB-Pad6)") (class "Default")
      (node (ref "U9") (pin "6") (pinfunction "TAB_6") (pintype "unspecified"))
    )
    (net (code "82") (name "unconnected-(U11-VOUT-Pad2)") (class "Default")
      (node (ref "U11") (pin "2") (pinfunction "VOUT_2") (pintype "unspecified"))
    )
    (net (code "83") (name "unconnected-(U13-EP-Pad29)") (class "Default")
      (node (ref "U13") (pin "29") (pinfunction "EP_29") (pintype "unspecified+no_connect"))
    )
    (net (code "84") (name "unconnected-(U13-NC-Pad10)") (class "Default")
      (node (ref "U13") (pin "10") (pinfunction "NC_10") (pintype "unspecified+no_connect"))
    )
    (net (code "85") (name "unconnected-(U13-NC-Pad13)") (class "Default")
      (node (ref "U13") (pin "13") (pinfunction "NC_13") (pintype "unspecified+no_connect"))
    )
    (net (code "86") (name "unconnected-(U13-NC-Pad14)") (class "Default")
      (node (ref "U13") (pin "14") (pinfunction "NC_14") (pintype "unspecified+no_connect"))
    )
    (net (code "87") (name "unconnected-(U13-NC-Pad15)") (class "Default")
      (node (ref "U13") (pin "15") (pinfunction "NC_15") (pintype "unspecified+no_connect"))
    )
    (net (code "88") (name "unconnected-(U13-NC-Pad16)") (class "Default")
      (node (ref "U13") (pin "16") (pinfunction "NC_16") (pintype "unspecified+no_connect"))
    )
    (net (code "89") (name "unconnected-(U13-NC-Pad17)") (class "Default")
      (node (ref "U13") (pin "17") (pinfunction "NC_17") (pintype "unspecified+no_connect"))
    )
    (net (code "90") (name "unconnected-(U13-NC-Pad18)") (class "Default")
      (node (ref "U13") (pin "18") (pinfunction "NC_18") (pintype "unspecified+no_connect"))
    )
    (net (code "91") (name "unconnected-(U13-NC-Pad19)") (class "Default")
      (node (ref "U13") (pin "19") (pinfunction "NC_19") (pintype "unspecified+no_connect"))
    )
    (net (code "92") (name "unconnected-(U13-NC-Pad20)") (class "Default")
      (node (ref "U13") (pin "20") (pinfunction "NC_20") (pintype "unspecified+no_connect"))
    )
    (net (code "93") (name "unconnected-(U13-NC-Pad21)") (class "Default")
      (node (ref "U13") (pin "21") (pinfunction "NC_21") (pintype "unspecified+no_connect"))
    )
    (net (code "94") (name "unconnected-(U13-NC-Pad22)") (class "Default")
      (node (ref "U13") (pin "22") (pinfunction "NC_22") (pintype "unspecified+no_connect"))
    )
    (net (code "95") (name "unconnected-(U13-SUSPEND-Pad12)") (class "Default")
      (node (ref "U13") (pin "12") (pinfunction "SUSPEND_12") (pintype "unspecified+no_connect"))
    )
    (net (code "96") (name "unconnected-(USB2-EH-Pad6)") (class "Default")
      (node (ref "USB2") (pin "6") (pinfunction "EH_6") (pintype "input"))
    )
    (net (code "97") (name "unconnected-(USB2-ID-Pad4)") (class "Default")
      (node (ref "USB2") (pin "4") (pinfunction "ID_4") (pintype "input+no_connect"))
    )
  )
)
